# PIR_Sensor_driver_v3.net
KiCad netlist of a schematic drawn in Altium Designer
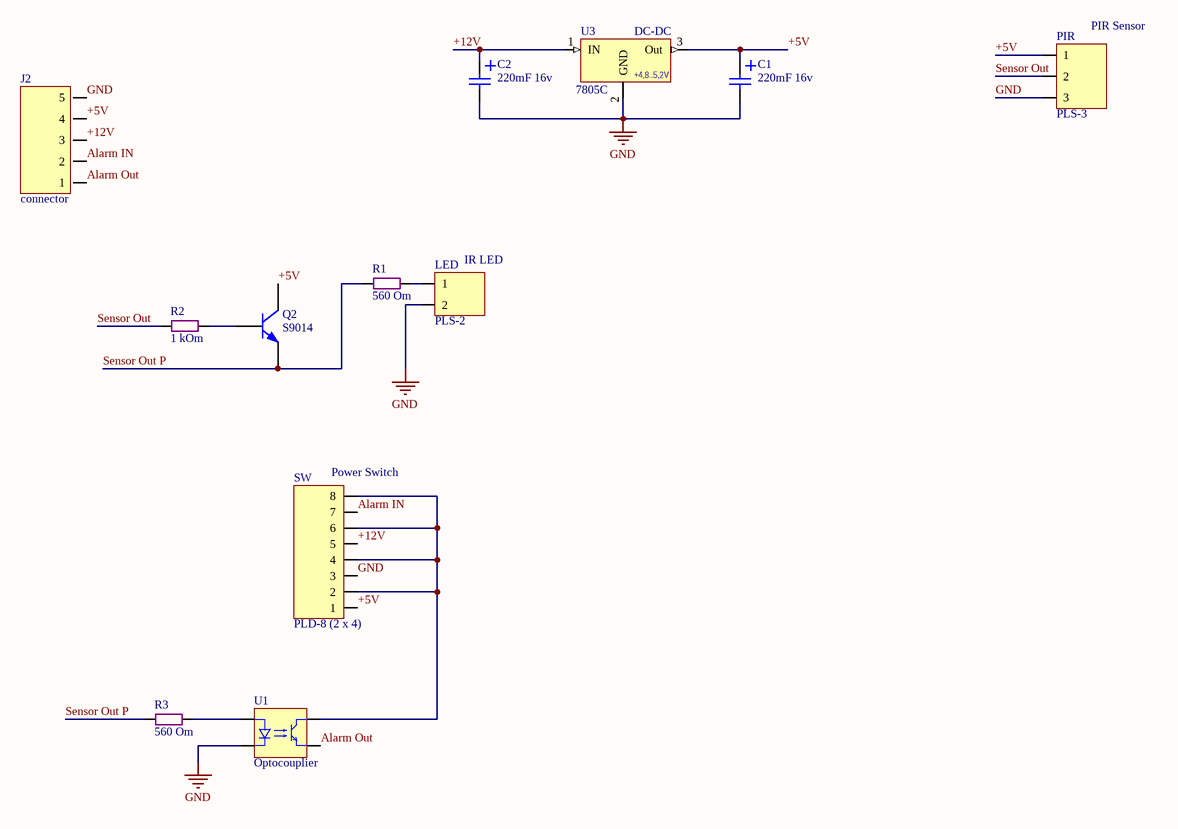
[diagram p0: PIR Sensor driver v3.SchDoc]

(export (version "E")
  (design (tool "Eeschema 10.0.6"))
  (components
    (comp (ref "C1")
      (value "220mF 16v")
      (footprint "Capacitor:Cap E p4mm D6.5xH11")
      (description "Capacitor")
      (libsource (lib "Capacitor") (part "Cap E 220mF x 16V"))
    )
    (comp (ref "C2")
      (value "220mF 16v")
      (footprint "Capacitor:Cap E p2mm D6.5xH11")
      (description "Capacitor")
      (libsource (lib "Capacitor") (part "Cap E 220mF x 16V"))
    )
    (comp (ref "J2")
      (value "connector")
      (footprint "Connector:Line 2.54 x 5 - (D2mm)")
      (description "Vert, Sgl line, Male")
      (libsource (lib "Connector") (part "PLS-5"))
    )
    (comp (ref "LED")
      (value "PLS-2")
      (footprint "Connector:Line 2.54 x 2")
      (description "Vert, Sgl line, Male")
      (libsource (lib "Connector") (part "PLS-2"))
    )
    (comp (ref "PIR")
      (value "PLS-3")
      (footprint "Connector:Line 2.54 X 3")
      (description "Vert, Sgl line, Male")
      (libsource (lib "Connector") (part "PLS-3"))
    )
    (comp (ref "Q2")
      (value "S9014")
      (footprint "GeneralCases:TO-92 2.54 (EBC)")
      (description "NPN Bipolar Transistor")
      (fields (field (name "PUBLISHER") "Altium Limited"))
      (libsource (lib "Transistor") (part "S9014"))
    )
    (comp (ref "R1")
      (value "560 Om")
      (footprint "SMD 0805 (2012)")
      (libsource (lib "PassiveComponents") (part "Res SMD 0805"))
    )
    (comp (ref "R2")
      (value "1 kOm")
      (footprint "SMD 0805 (2012)")
      (libsource (lib "PassiveComponents") (part "Res SMD 0805"))
    )
    (comp (ref "R3")
      (value "560 Om")
      (footprint "SMD 0805 (2012)")
      (libsource (lib "PassiveComponents") (part "Res SMD 0805"))
    )
    (comp (ref "SW")
      (value "PLD-8 (2 x 4)")
      (footprint "Connector:Line 2.54 X 8D (2 x 4)")
      (description "Vert, Sgl line, Male")
      (libsource (lib "Connector") (part "PLD-8 (2 x 4)"))
    )
    (comp (ref "U1")
      (value "Optocouplier")
      (footprint "GeneralCases:DIP-4")
      (libsource (lib "Transistor") (part "Optocouplier LTV 817B"))
    )
    (comp (ref "U3")
      (value "7805C")
      (footprint "GeneralCases:D-PAK")
      (description "Voltage Regulator")
      (fields (field (name "MANUFACTURER") "Интеграл") (field (name "V OUT") "+4,8..5,2V"))
      (libsource (lib "PowerAdjusment") (part "7805C"))
    )
  )
  (nets
    (net (code "1") (name "/+5V") (class "Default")
      (node (ref "C1") (pin "1") (pinfunction "1_1") (pintype "passive"))
      (node (ref "J2") (pin "4") (pinfunction "4_4") (pintype "passive"))
      (node (ref "PIR") (pin "1") (pinfunction "1_1") (pintype "passive"))
      (node (ref "Q2") (pin "C") (pinfunction "C_C") (pintype "passive"))
      (node (ref "SW") (pin "1") (pinfunction "1_1") (pintype "passive"))
      (node (ref "U3") (pin "3") (pinfunction "Out_3") (pintype "output"))
    )
    (net (code "2") (name "/+12V") (class "Default")
      (node (ref "C2") (pin "1") (pinfunction "1_1") (pintype "passive"))
      (node (ref "J2") (pin "3") (pinfunction "3_3") (pintype "passive"))
      (node (ref "SW") (pin "5") (pinfunction "5_5") (pintype "passive"))
      (node (ref "U3") (pin "1") (pinfunction "IN_1") (pintype "input"))
    )
    (net (code "3") (name "/Alarm IN") (class "Default")
      (node (ref "J2") (pin "2") (pinfunction "2_2") (pintype "passive"))
      (node (ref "SW") (pin "7") (pinfunction "7_7") (pintype "passive"))
    )
    (net (code "4") (name "/Alarm Out") (class "Default")
      (node (ref "J2") (pin "1") (pinfunction "1_1") (pintype "passive"))
      (node (ref "U1") (pin "4") (pinfunction "4_4") (pintype "passive"))
    )
    (net (code "5") (name "/Sensor Out") (class "Default")
      (node (ref "PIR") (pin "2") (pinfunction "2_2") (pintype "passive"))
      (node (ref "R2") (pin "1") (pinfunction "1_1") (pintype "passive"))
    )
    (net (code "6") (name "/Sensor Out P") (class "Default")
      (node (ref "Q2") (pin "E") (pinfunction "E_E") (pintype "passive"))
      (node (ref "R1") (pin "1") (pinfunction "1_1") (pintype "passive"))
      (node (ref "R3") (pin "1") (pinfunction "1_1") (pintype "passive"))
    )
    (net (code "7") (name "GND") (class "Default")
      (node (ref "C1") (pin "2") (pinfunction "2_2") (pintype "passive"))
      (node (ref "C2") (pin "2") (pinfunction "2_2") (pintype "passive"))
      (node (ref "J2") (pin "5") (pinfunction "5_5") (pintype "passive"))
      (node (ref "LED") (pin "2") (pinfunction "2_2") (pintype "passive"))
      (node (ref "PIR") (pin "3") (pinfunction "3_3") (pintype "passive"))
      (node (ref "SW") (pin "3") (pinfunction "3_3") (pintype "passive"))
      (node (ref "U1") (pin "2") (pinfunction "2_2") (pintype "passive"))
      (node (ref "U3") (pin "2") (pinfunction "GND_2") (pintype "passive"))
    )
    (net (code "8") (name "Net-(LED-Pad1)") (class "Default")
      (node (ref "LED") (pin "1") (pinfunction "1_1") (pintype "passive"))
      (node (ref "R1") (pin "2") (pinfunction "2_2") (pintype "passive"))
    )
    (net (code "9") (name "Net-(Q2-PadB)") (class "Default")
      (node (ref "Q2") (pin "B") (pinfunction "B_B") (pintype "passive"))
      (node (ref "R2") (pin "2") (pinfunction "2_2") (pintype "passive"))
    )
    (net (code "10") (name "Net-(R3-Pad2)") (class "Default")
      (node (ref "R3") (pin "2") (pinfunction "2_2") (pintype "passive"))
      (node (ref "U1") (pin "1") (pinfunction "1_1") (pintype "passive"))
    )
    (net (code "11") (name "Net-(SW-Pad2)") (class "Default")
      (node (ref "SW") (pin "2") (pinfunction "2_2") (pintype "passive"))
      (node (ref "SW") (pin "4") (pinfunction "4_4") (pintype "passive"))
      (node (ref "SW") (pin "6") (pinfunction "6_6") (pintype "passive"))
      (node (ref "SW") (pin "8") (pinfunction "8_8") (pintype "passive"))
      (node (ref "U1") (pin "3") (pinfunction "3_3") (pintype "passive"))
    )
  )
)
